# DS145-1_0-B.net
KiCad netlist of a schematic drawn in Altium Designer
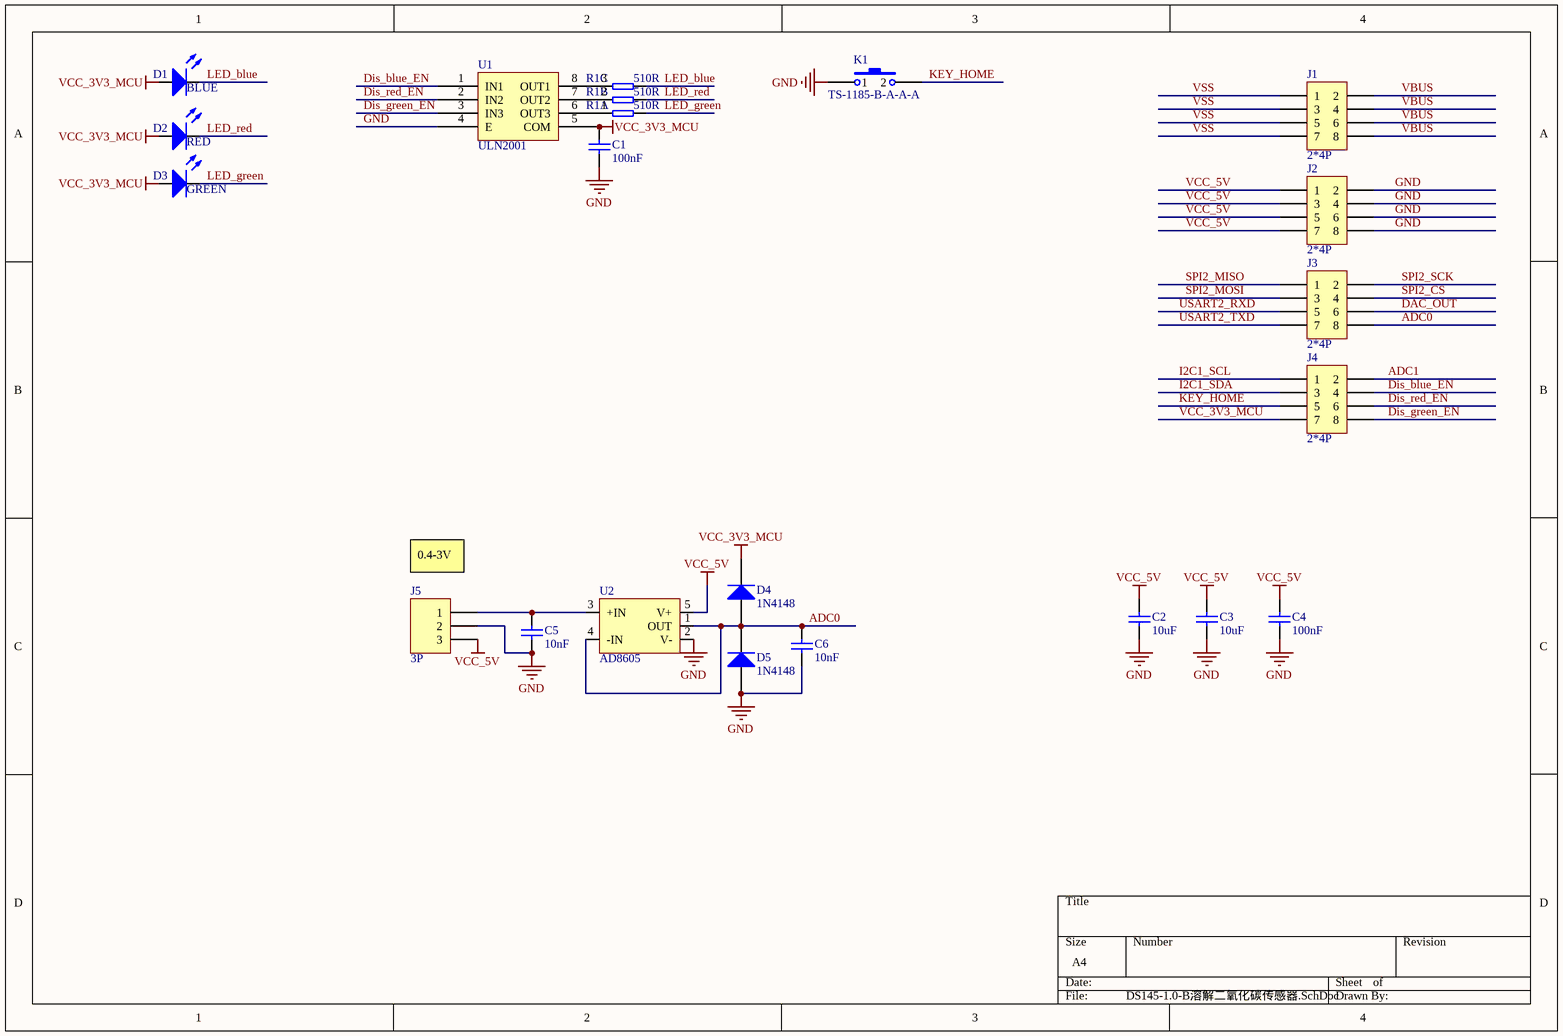
[diagram p0: DS145-1.0-B溶解二氧化碳传感器.SchDoc]

(export (version "E")
  (design (tool "Eeschema 10.0.6"))
  (components
    (comp (ref "C1")
      (value "100nF")
      (footprint "0603CAP")
      (description "贴片电容")
      (fields (field (name "Comment") "SMDCAP00013"))
      (libsource (lib "AD_SCH") (part "MLCC 100nF 50V ±10％ 0603"))
    )
    (comp (ref "C2")
      (value "10uF")
      (footprint "0603CAP")
      (description "贴片电容")
      (fields (field (name "Comment") "SMDCAP00016"))
      (libsource (lib "AD_SCH") (part "MLCC 10uF 50V ±10％ 0603"))
    )
    (comp (ref "C3")
      (value "10uF")
      (footprint "0603CAP")
      (description "贴片电容")
      (fields (field (name "Comment") "SMDCAP00016"))
      (libsource (lib "AD_SCH") (part "MLCC 10uF 50V ±10％ 0603"))
    )
    (comp (ref "C4")
      (value "100nF")
      (footprint "0603CAP")
      (description "贴片电容")
      (fields (field (name "Comment") "SMDCAP00013"))
      (libsource (lib "AD_SCH") (part "MLCC 100nF 50V ±10％ 0603"))
    )
    (comp (ref "C5")
      (value "10nF")
      (footprint "0603CAP")
      (description "贴片电容")
      (fields (field (name "Comment") "SMDCAP00013"))
      (libsource (lib "AD_SCH") (part "MLCC 100nF 50V ±10％ 0603"))
    )
    (comp (ref "C6")
      (value "10nF")
      (footprint "0603CAP")
      (description "贴片电容")
      (fields (field (name "Comment") "SMDCAP00010"))
      (libsource (lib "AD_SCH") (part "MLCC 10nF 50V ±10％ 0603"))
    )
    (comp (ref "D1")
      (value "BLUE")
      (footprint "LED_0805")
      (description "贴片LED")
      (fields (field (name "Comment") "SMDLED00010"))
      (libsource (lib "AD_SCH") (part "Chip 蓝色LED 0805"))
    )
    (comp (ref "D2")
      (value "RED")
      (footprint "LED_0805")
      (description "贴片LED")
      (fields (field (name "Comment") "SMDLED00003"))
      (libsource (lib "AD_SCH") (part "Chip 红色LED 0805"))
    )
    (comp (ref "D3")
      (value "GREEN")
      (footprint "LED_0805")
      (description "贴片LED")
      (fields (field (name "Comment") "Chip 翠绿LED 0805"))
      (libsource (lib "AD_SCH") (part "Chip 翠绿LED 0805"))
    )
    (comp (ref "D4")
      (value "1N4148")
      (footprint "SOD-123")
      (description "贴片开关二极管 T4")
      (fields (field (name "Comment") "DIPDIODE02001"))
      (libsource (lib "AD_SCH") (part "1N4148W"))
    )
    (comp (ref "D5")
      (value "1N4148")
      (footprint "SOD-123")
      (description "贴片开关二极管 T4")
      (fields (field (name "Comment") "DIPDIODE02001"))
      (libsource (lib "AD_SCH") (part "1N4148W"))
    )
    (comp (ref "J1")
      (value "2*4P")
      (footprint "X1321WVS-2x04J-C40D53")
      (description "双排针2x4P 立贴 1.27mm")
      (fields (field (name "Comment") "X1321WVS-2x04J-C40D53"))
      (libsource (lib "AD_SCH") (part "X1321WVS-2x04J-C40D53"))
    )
    (comp (ref "J2")
      (value "2*4P")
      (footprint "X1321WVS-2x04J-C40D53")
      (description "双排针2x4P 立贴 1.27mm")
      (fields (field (name "Comment") "X1321WVS-2x04J-C40D53"))
      (libsource (lib "AD_SCH") (part "X1321WVS-2x04J-C40D53"))
    )
    (comp (ref "J3")
      (value "2*4P")
      (footprint "X1321WVS-2x04J-C40D53")
      (description "双排针2x4P 立贴 1.27mm")
      (fields (field (name "Comment") "X1321WVS-2x04J-C40D53"))
      (libsource (lib "AD_SCH") (part "X1321WVS-2x04J-C40D53"))
    )
    (comp (ref "J4")
      (value "2*4P")
      (footprint "X1321WVS-2x04J-C40D53")
      (description "双排针2x4P 立贴 1.27mm")
      (fields (field (name "Comment") "X1321WVS-2x04J-C40D53"))
      (libsource (lib "AD_SCH") (part "X1321WVS-2x04J-C40D53"))
    )
    (comp (ref "J5")
      (value "3P")
      (footprint "SIP3")
      (description "单排直针")
      (fields (field (name "Comment") "SL000000042"))
      (libsource (lib "AD_SCH") (part "DIP3 单排直针 间距2.54mm 针长11mm 铜"))
    )
    (comp (ref "K1")
      (value "TS-1185-B-A-A-A")
      (footprint "KEY_TS-1185-x-A-A-A")
      (description "轻触开关")
      (libsource (lib "AD_SCH") (part "TS-1185-B-A-A-A"))
    )
    (comp (ref "R1")
      (value "510R")
      (footprint "0603RES_Pack4")
      (description "贴片排阻")
      (fields (field (name "Comment") "SMDRES05003"))
      (libsource (lib "AD_SCH") (part "Chip R*4 510R 1/16W ±5％ 0603"))
    )
    (comp (ref "U1")
      (value "ULN2001")
      (footprint "SO-8")
      (description "电机驱动芯片")
      (fields (field (name "Comment") "SMDIC000018"))
      (libsource (lib "AD_SCH") (part "ULN2001 SOP-8"))
    )
    (comp (ref "U2")
      (value "AD8605")
      (footprint "SOT23-5")
      (description "运放芯片")
      (libsource (lib "AD_SCH") (part "AD8605 SOT23-5"))
    )
  )
  (nets
    (net (code "1") (name "/ADC0") (class "Default")
      (node (ref "C6") (pin "2") (pinfunction "2_2") (pintype "passive"))
      (node (ref "D4") (pin "1") (pinfunction "A_1") (pintype "passive"))
      (node (ref "D5") (pin "2") (pinfunction "K_2") (pintype "passive"))
      (node (ref "J3") (pin "8") (pinfunction "8_8") (pintype "passive"))
      (node (ref "U2") (pin "1") (pinfunction "OUT_1") (pintype "passive"))
      (node (ref "U2") (pin "4") (pinfunction "-IN_4") (pintype "passive"))
    )
    (net (code "2") (name "/ADC1") (class "Default")
      (node (ref "J4") (pin "2") (pinfunction "2_2") (pintype "passive"))
    )
    (net (code "3") (name "/DAC_OUT") (class "Default")
      (node (ref "J3") (pin "6") (pinfunction "6_6") (pintype "passive"))
    )
    (net (code "4") (name "/Dis_blue_EN") (class "Default")
      (node (ref "J4") (pin "4") (pinfunction "4_4") (pintype "passive"))
      (node (ref "U1") (pin "1") (pinfunction "IN1_1") (pintype "passive"))
    )
    (net (code "5") (name "/Dis_green_EN") (class "Default")
      (node (ref "J4") (pin "8") (pinfunction "8_8") (pintype "passive"))
      (node (ref "U1") (pin "3") (pinfunction "IN3_3") (pintype "passive"))
    )
    (net (code "6") (name "/Dis_red_EN") (class "Default")
      (node (ref "J4") (pin "6") (pinfunction "6_6") (pintype "passive"))
      (node (ref "U1") (pin "2") (pinfunction "IN2_2") (pintype "passive"))
    )
    (net (code "7") (name "/I2C1_SCL") (class "Default")
      (node (ref "J4") (pin "1") (pinfunction "1_1") (pintype "passive"))
    )
    (net (code "8") (name "/I2C1_SDA") (class "Default")
      (node (ref "J4") (pin "3") (pinfunction "3_3") (pintype "passive"))
    )
    (net (code "9") (name "/KEY_HOME") (class "Default")
      (node (ref "J4") (pin "5") (pinfunction "5_5") (pintype "passive"))
      (node (ref "K1") (pin "2") (pinfunction "2_2") (pintype "passive"))
    )
    (net (code "10") (name "/LED_blue") (class "Default")
      (node (ref "D1") (pin "2") (pinfunction "K_2") (pintype "passive"))
      (node (ref "R1") (pin "6") (pinfunction "6_6") (pintype "passive"))
    )
    (net (code "11") (name "/LED_green") (class "Default")
      (node (ref "D3") (pin "2") (pinfunction "K_2") (pintype "passive"))
      (node (ref "R1") (pin "8") (pinfunction "8_8") (pintype "passive"))
    )
    (net (code "12") (name "/LED_red") (class "Default")
      (node (ref "D2") (pin "2") (pinfunction "K_2") (pintype "passive"))
      (node (ref "R1") (pin "7") (pinfunction "7_7") (pintype "passive"))
    )
    (net (code "13") (name "/SPI2_CS") (class "Default")
      (node (ref "J3") (pin "4") (pinfunction "4_4") (pintype "passive"))
    )
    (net (code "14") (name "/SPI2_MISO") (class "Default")
      (node (ref "J3") (pin "1") (pinfunction "1_1") (pintype "passive"))
    )
    (net (code "15") (name "/SPI2_MOSI") (class "Default")
      (node (ref "J3") (pin "3") (pinfunction "3_3") (pintype "passive"))
    )
    (net (code "16") (name "/SPI2_SCK") (class "Default")
      (node (ref "J3") (pin "2") (pinfunction "2_2") (pintype "passive"))
    )
    (net (code "17") (name "/USART2_RXD") (class "Default")
      (node (ref "J3") (pin "5") (pinfunction "5_5") (pintype "passive"))
    )
    (net (code "18") (name "/USART2_TXD") (class "Default")
      (node (ref "J3") (pin "7") (pinfunction "7_7") (pintype "passive"))
    )
    (net (code "19") (name "/VBUS") (class "Default")
      (node (ref "J1") (pin "2") (pinfunction "2_2") (pintype "passive"))
      (node (ref "J1") (pin "4") (pinfunction "4_4") (pintype "passive"))
      (node (ref "J1") (pin "6") (pinfunction "6_6") (pintype "passive"))
      (node (ref "J1") (pin "8") (pinfunction "8_8") (pintype "passive"))
    )
    (net (code "20") (name "/VSS") (class "Default")
      (node (ref "J1") (pin "1") (pinfunction "1_1") (pintype "passive"))
      (node (ref "J1") (pin "3") (pinfunction "3_3") (pintype "passive"))
      (node (ref "J1") (pin "5") (pinfunction "5_5") (pintype "passive"))
      (node (ref "J1") (pin "7") (pinfunction "7_7") (pintype "passive"))
    )
    (net (code "21") (name "GND") (class "Default")
      (node (ref "C1") (pin "1") (pinfunction "1_1") (pintype "passive"))
      (node (ref "C2") (pin "1") (pinfunction "1_1") (pintype "passive"))
      (node (ref "C3") (pin "1") (pinfunction "1_1") (pintype "passive"))
      (node (ref "C4") (pin "1") (pinfunction "1_1") (pintype "passive"))
      (node (ref "C5") (pin "1") (pinfunction "1_1") (pintype "passive"))
      (node (ref "C6") (pin "1") (pinfunction "1_1") (pintype "passive"))
      (node (ref "D5") (pin "1") (pinfunction "A_1") (pintype "passive"))
      (node (ref "J2") (pin "2") (pinfunction "2_2") (pintype "passive"))
      (node (ref "J2") (pin "4") (pinfunction "4_4") (pintype "passive"))
      (node (ref "J2") (pin "6") (pinfunction "6_6") (pintype "passive"))
      (node (ref "J2") (pin "8") (pinfunction "8_8") (pintype "passive"))
      (node (ref "J5") (pin "2") (pinfunction "2_2") (pintype "passive"))
      (node (ref "K1") (pin "1") (pinfunction "1_1") (pintype "passive"))
      (node (ref "U1") (pin "4") (pinfunction "E_4") (pintype "passive"))
      (node (ref "U2") (pin "2") (pinfunction "V-_2") (pintype "passive"))
    )
    (net (code "22") (name "Net-(U1-OUT1)") (class "Default")
      (node (ref "R1") (pin "3") (pinfunction "3_3") (pintype "passive"))
      (node (ref "U1") (pin "8") (pinfunction "OUT1_8") (pintype "passive"))
    )
    (net (code "23") (name "Net-(U1-OUT2)") (class "Default")
      (node (ref "R1") (pin "2") (pinfunction "2_2") (pintype "passive"))
      (node (ref "U1") (pin "7") (pinfunction "OUT2_7") (pintype "passive"))
    )
    (net (code "24") (name "Net-(U1-OUT3)") (class "Default")
      (node (ref "R1") (pin "1") (pinfunction "1_1") (pintype "passive"))
      (node (ref "U1") (pin "6") (pinfunction "OUT3_6") (pintype "passive"))
    )
    (net (code "25") (name "Net-(U2-+IN)") (class "Default")
      (node (ref "C5") (pin "2") (pinfunction "2_2") (pintype "passive"))
      (node (ref "J5") (pin "1") (pinfunction "1_1") (pintype "passive"))
      (node (ref "U2") (pin "3") (pinfunction "+IN_3") (pintype "passive"))
    )
    (net (code "26") (name "VCC_3V3_MCU") (class "Default")
      (node (ref "C1") (pin "2") (pinfunction "2_2") (pintype "passive"))
      (node (ref "D1") (pin "1") (pinfunction "A_1") (pintype "passive"))
      (node (ref "D2") (pin "1") (pinfunction "A_1") (pintype "passive"))
      (node (ref "D3") (pin "1") (pinfunction "A_1") (pintype "passive"))
      (node (ref "D4") (pin "2") (pinfunction "K_2") (pintype "passive"))
      (node (ref "J4") (pin "7") (pinfunction "7_7") (pintype "passive"))
      (node (ref "U1") (pin "5") (pinfunction "COM_5") (pintype "passive"))
    )
    (net (code "27") (name "VCC_5V") (class "Default")
      (node (ref "C2") (pin "2") (pinfunction "2_2") (pintype "passive"))
      (node (ref "C3") (pin "2") (pinfunction "2_2") (pintype "passive"))
      (node (ref "C4") (pin "2") (pinfunction "2_2") (pintype "passive"))
      (node (ref "J2") (pin "1") (pinfunction "1_1") (pintype "passive"))
      (node (ref "J2") (pin "3") (pinfunction "3_3") (pintype "passive"))
      (node (ref "J2") (pin "5") (pinfunction "5_5") (pintype "passive"))
      (node (ref "J2") (pin "7") (pinfunction "7_7") (pintype "passive"))
      (node (ref "J5") (pin "3") (pinfunction "3_3") (pintype "passive"))
      (node (ref "U2") (pin "5") (pinfunction "V+_5") (pintype "passive"))
    )
  )
)
